# MainBoard_Schematic.net
KiCad netlist of a schematic drawn in Altium Designer
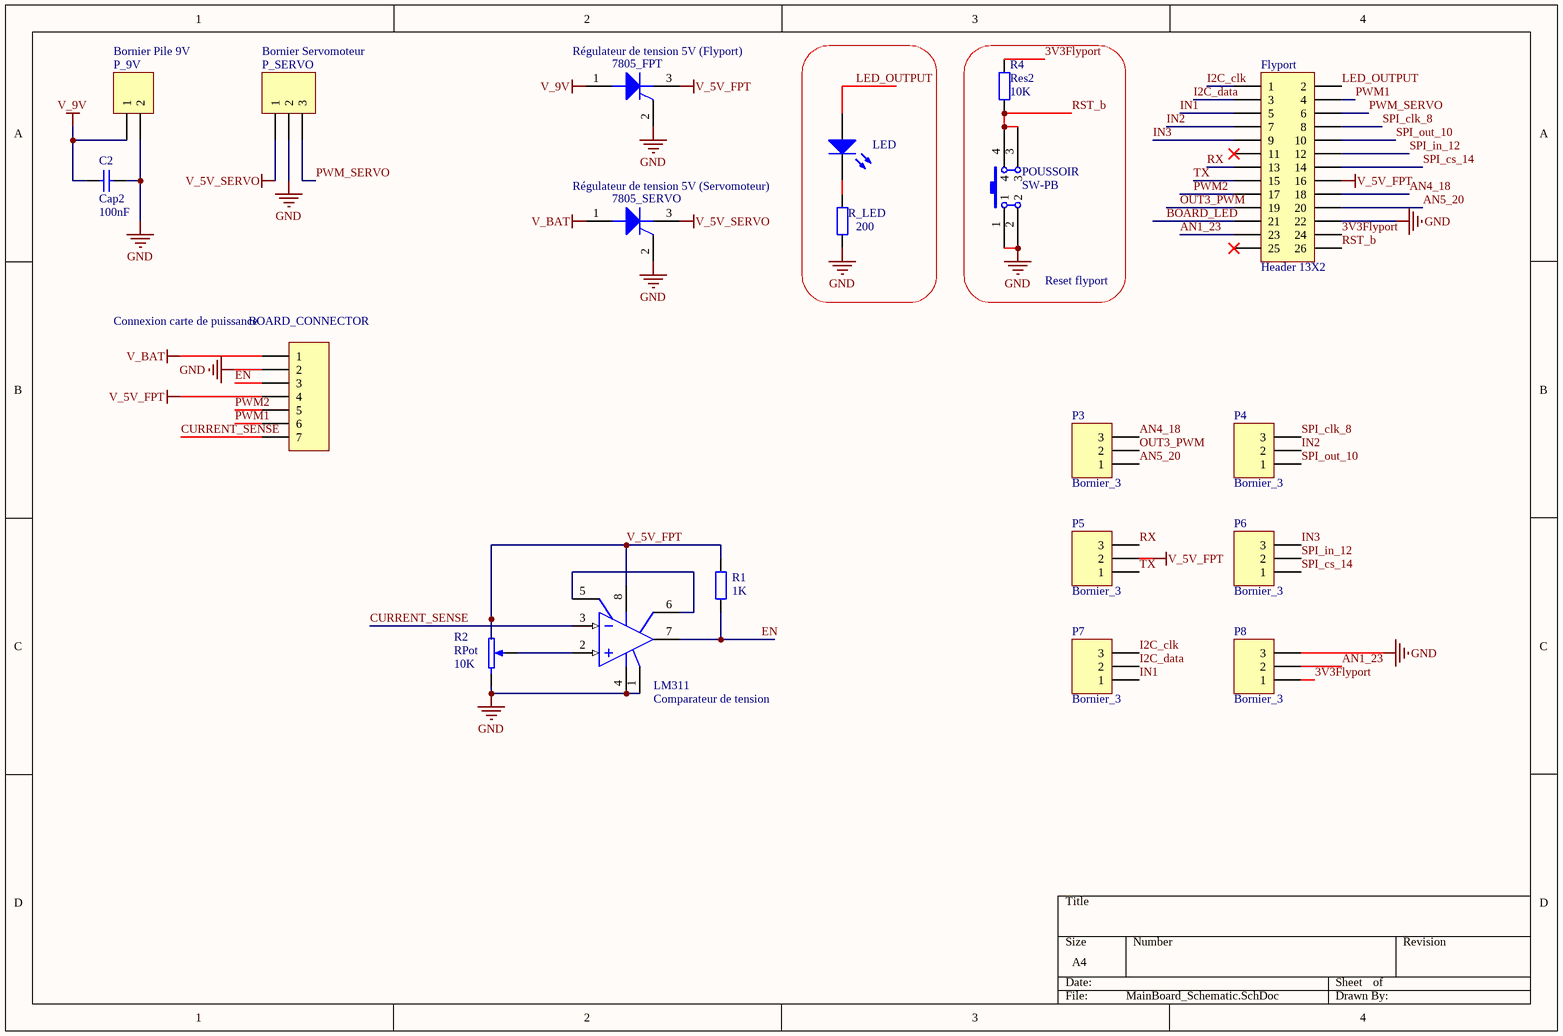
[diagram p0: MainBoard_Schematic.SchDoc]

(export (version "E")
  (design (tool "Eeschema 10.0.6"))
  (components
    (comp (ref "7805_FPT")
      (value "Régulateur de tension 5V (Flyport)")
      (footprint "TO-220-AB")
      (description "Silicon Controlled Rectifier")
      (fields (field (name "PUBLISHER") "Altium Limited"))
      (libsource (lib "Miscellaneous Devices") (part "SCR"))
    )
    (comp (ref "7805_SERVO")
      (value "Régulateur de tension 5V (Servomoteur)")
      (footprint "TO-220-AB")
      (description "Silicon Controlled Rectifier")
      (fields (field (name "PUBLISHER") "Altium Limited"))
      (libsource (lib "Miscellaneous Devices") (part "SCR"))
    )
    (comp (ref "BOARD_CONNECTOR")
      (value "Connexion carte de puissance")
      (footprint "HDR1X7")
      (description "Header, 7-Pin")
      (fields (field (name "PUBLISHER") "Altium Limited"))
      (libsource (lib "Miscellaneous Connectors") (part "Header 7"))
    )
    (comp (ref "C2")
      (value "Cap2")
      (footprint "CAPA2")
      (description "Capacitor")
      (fields (field (name "ALTIUM_VALUE") "100nF") (field (name "PUBLISHER") "Altium Limited"))
      (libsource (lib "LIBRAIRIE_INTEGREE_PHELMA1") (part "Cap2"))
    )
    (comp (ref "Flyport")
      (value "Header 13X2")
      (footprint "HDR2X13")
      (description "Header, 13-Pin, Dual row")
      (fields (field (name "PUBLISHER") "Altium Limited"))
      (libsource (lib "Miscellaneous Connectors") (part "Header 13X2"))
    )
    (comp (ref "LED")
      (value "Led")
      (footprint "LED")
      (description "LED")
      (fields (field (name "PUBLISHER") "Altium Limited"))
      (libsource (lib "LIBRAIRIE_INTEGREE_PHELMA1") (part "Led"))
    )
    (comp (ref "LM311")
      (value "Comparateur de tension")
      (footprint "LIBRAIRIE_INTEGREE_PHELMA1:DIP8")
      (description "Voltage Comparator")
      (fields (field (name "PUBLISHER") "Altium Limited"))
      (libsource (lib "LIBRAIRIE_INTEGREE_PHELMA1") (part "LM311N"))
    )
    (comp (ref "P3")
      (value "Bornier_3")
      (footprint "Bornier_3")
      (description "Header, 3-Pin")
      (fields (field (name "PUBLISHER") "Altium Limited"))
      (libsource (lib "INTEGRATED_LIBRARY1_CONNECTEURS") (part "Bornier_3"))
    )
    (comp (ref "P4")
      (value "Bornier_3")
      (footprint "Bornier_3")
      (description "Header, 3-Pin")
      (fields (field (name "PUBLISHER") "Altium Limited"))
      (libsource (lib "INTEGRATED_LIBRARY1_CONNECTEURS") (part "Bornier_3"))
    )
    (comp (ref "P5")
      (value "Bornier_3")
      (footprint "Bornier_3")
      (description "Header, 3-Pin")
      (fields (field (name "PUBLISHER") "Altium Limited"))
      (libsource (lib "INTEGRATED_LIBRARY1_CONNECTEURS") (part "Bornier_3"))
    )
    (comp (ref "P6")
      (value "Bornier_3")
      (footprint "Bornier_3")
      (description "Header, 3-Pin")
      (fields (field (name "PUBLISHER") "Altium Limited"))
      (libsource (lib "INTEGRATED_LIBRARY1_CONNECTEURS") (part "Bornier_3"))
    )
    (comp (ref "P7")
      (value "Bornier_3")
      (footprint "Bornier_3")
      (description "Header, 3-Pin")
      (fields (field (name "PUBLISHER") "Altium Limited"))
      (libsource (lib "INTEGRATED_LIBRARY1_CONNECTEURS") (part "Bornier_3"))
    )
    (comp (ref "P8")
      (value "Bornier_3")
      (footprint "Bornier_3")
      (description "Header, 3-Pin")
      (fields (field (name "PUBLISHER") "Altium Limited"))
      (libsource (lib "INTEGRATED_LIBRARY1_CONNECTEURS") (part "Bornier_3"))
    )
    (comp (ref "POUSSOIR")
      (value "SW-PB")
      (footprint "SW_BP")
      (description "Switch")
      (fields (field (name "PUBLISHER") "Altium Limited"))
      (libsource (lib "INTEGRATED_LIBRARY1_CONNECTEURS") (part "SW-PB"))
    )
    (comp (ref "P_9V")
      (value "Bornier Pile 9V")
      (footprint "Bornier_2")
      (description "Header, 2-Pin")
      (fields (field (name "PUBLISHER") "Altium Limited"))
      (libsource (lib "INTEGRATED_LIBRARY1_CONNECTEURS") (part "Bornier_2"))
    )
    (comp (ref "P_SERVO")
      (value "Bornier Servomoteur")
      (footprint "Bornier_3")
      (description "Header, 3-Pin")
      (fields (field (name "PUBLISHER") "Altium Limited"))
      (libsource (lib "") (part "Bornier_3_1"))
    )
    (comp (ref "R1")
      (value "1K")
      (footprint "res5_1/4W")
      (description "Resistor")
      (fields (field (name "Comment") "Res2") (field (name "PUBLISHER") "Altium Limited"))
      (libsource (lib "LIBRAIRIE_INTEGREE_PHELMA1") (part "Res2"))
    )
    (comp (ref "R2")
      (value "RPot")
      (footprint "AJUSTABLE")
      (description "Potentiometer")
      (fields (field (name "ALTIUM_VALUE") "10K") (field (name "PUBLISHER") "Altium Limited"))
      (libsource (lib "LIBRAIRIE_INTEGREE_PHELMA1") (part "RPot"))
    )
    (comp (ref "R4")
      (value "Res2")
      (footprint "res5_1/4W")
      (description "Resistor")
      (fields (field (name "ALTIUM_VALUE") "10K") (field (name "PUBLISHER") "Altium Limited"))
      (libsource (lib "") (part "Res2_1"))
    )
    (comp (ref "R_LED")
      (value "200")
      (footprint "res5_1/4W")
      (description "Resistor")
      (fields (field (name "PUBLISHER") "Altium Limited"))
      (libsource (lib "") (part "Res2_1"))
    )
  )
  (nets
    (net (code "1") (name "/3V3Flyport") (class "Default")
      (node (ref "Flyport") (pin "24") (pinfunction "24_24") (pintype "passive"))
      (node (ref "P8") (pin "1") (pinfunction "1_1") (pintype "passive"))
      (node (ref "R4") (pin "1") (pinfunction "1_1") (pintype "passive"))
    )
    (net (code "2") (name "/AN1_23") (class "Default")
      (node (ref "Flyport") (pin "23") (pinfunction "23_23") (pintype "passive"))
      (node (ref "P8") (pin "2") (pinfunction "2_2") (pintype "passive"))
    )
    (net (code "3") (name "/AN4_18") (class "Default")
      (node (ref "Flyport") (pin "18") (pinfunction "18_18") (pintype "passive"))
      (node (ref "P3") (pin "3") (pinfunction "3_3") (pintype "passive"))
    )
    (net (code "4") (name "/AN5_20") (class "Default")
      (node (ref "Flyport") (pin "20") (pinfunction "20_20") (pintype "passive"))
      (node (ref "P3") (pin "1") (pinfunction "1_1") (pintype "passive"))
    )
    (net (code "5") (name "/BOARD_LED") (class "Default")
      (node (ref "Flyport") (pin "21") (pinfunction "21_21") (pintype "passive"))
    )
    (net (code "6") (name "/CURRENT_SENSE") (class "Default")
      (node (ref "BOARD_CONNECTOR") (pin "7") (pinfunction "7_7") (pintype "passive"))
      (node (ref "LM311") (pin "3") (pinfunction "IN-_3") (pintype "input"))
    )
    (net (code "7") (name "/EN") (class "Default")
      (node (ref "BOARD_CONNECTOR") (pin "3") (pinfunction "3_3") (pintype "passive"))
      (node (ref "LM311") (pin "7") (pinfunction "OUT_7") (pintype "open_collector"))
      (node (ref "R1") (pin "1") (pinfunction "1_1") (pintype "passive"))
    )
    (net (code "8") (name "/I2C_clk") (class "Default")
      (node (ref "Flyport") (pin "1") (pinfunction "1_1") (pintype "passive"))
      (node (ref "P7") (pin "3") (pinfunction "3_3") (pintype "passive"))
    )
    (net (code "9") (name "/I2C_data") (class "Default")
      (node (ref "Flyport") (pin "3") (pinfunction "3_3") (pintype "passive"))
      (node (ref "P7") (pin "2") (pinfunction "2_2") (pintype "passive"))
    )
    (net (code "10") (name "/IN1") (class "Default")
      (node (ref "Flyport") (pin "5") (pinfunction "5_5") (pintype "passive"))
      (node (ref "P7") (pin "1") (pinfunction "1_1") (pintype "passive"))
    )
    (net (code "11") (name "/IN2") (class "Default")
      (node (ref "Flyport") (pin "7") (pinfunction "7_7") (pintype "passive"))
      (node (ref "P4") (pin "2") (pinfunction "2_2") (pintype "passive"))
    )
    (net (code "12") (name "/IN3") (class "Default")
      (node (ref "Flyport") (pin "9") (pinfunction "9_9") (pintype "passive"))
      (node (ref "P6") (pin "3") (pinfunction "3_3") (pintype "passive"))
    )
    (net (code "13") (name "/LED_OUTPUT") (class "Default")
      (node (ref "Flyport") (pin "2") (pinfunction "2_2") (pintype "passive"))
      (node (ref "LED") (pin "1") (pinfunction "A_1") (pintype "passive"))
    )
    (net (code "14") (name "/OUT3_PWM") (class "Default")
      (node (ref "Flyport") (pin "19") (pinfunction "19_19") (pintype "passive"))
      (node (ref "P3") (pin "2") (pinfunction "2_2") (pintype "passive"))
    )
    (net (code "15") (name "/PWM1") (class "Default")
      (node (ref "BOARD_CONNECTOR") (pin "6") (pinfunction "6_6") (pintype "passive"))
      (node (ref "Flyport") (pin "4") (pinfunction "4_4") (pintype "passive"))
    )
    (net (code "16") (name "/PWM2") (class "Default")
      (node (ref "BOARD_CONNECTOR") (pin "5") (pinfunction "5_5") (pintype "passive"))
      (node (ref "Flyport") (pin "17") (pinfunction "17_17") (pintype "passive"))
    )
    (net (code "17") (name "/PWM_SERVO") (class "Default")
      (node (ref "Flyport") (pin "6") (pinfunction "6_6") (pintype "passive"))
      (node (ref "P_SERVO") (pin "3") (pinfunction "3_3") (pintype "passive"))
    )
    (net (code "18") (name "/RST_b") (class "Default")
      (node (ref "Flyport") (pin "26") (pinfunction "26_26") (pintype "passive"))
      (node (ref "POUSSOIR") (pin "3") (pinfunction "3_3") (pintype "passive"))
      (node (ref "POUSSOIR") (pin "4") (pinfunction "4_4") (pintype "passive"))
      (node (ref "R4") (pin "2") (pinfunction "2_2") (pintype "passive"))
    )
    (net (code "19") (name "/RX") (class "Default")
      (node (ref "Flyport") (pin "13") (pinfunction "13_13") (pintype "passive"))
      (node (ref "P5") (pin "3") (pinfunction "3_3") (pintype "passive"))
    )
    (net (code "20") (name "/SPI_clk_8") (class "Default")
      (node (ref "Flyport") (pin "8") (pinfunction "8_8") (pintype "passive"))
      (node (ref "P4") (pin "3") (pinfunction "3_3") (pintype "passive"))
    )
    (net (code "21") (name "/SPI_cs_14") (class "Default")
      (node (ref "Flyport") (pin "14") (pinfunction "14_14") (pintype "passive"))
      (node (ref "P6") (pin "1") (pinfunction "1_1") (pintype "passive"))
    )
    (net (code "22") (name "/SPI_in_12") (class "Default")
      (node (ref "Flyport") (pin "12") (pinfunction "12_12") (pintype "passive"))
      (node (ref "P6") (pin "2") (pinfunction "2_2") (pintype "passive"))
    )
    (net (code "23") (name "/SPI_out_10") (class "Default")
      (node (ref "Flyport") (pin "10") (pinfunction "10_10") (pintype "passive"))
      (node (ref "P4") (pin "1") (pinfunction "1_1") (pintype "passive"))
    )
    (net (code "24") (name "/TX") (class "Default")
      (node (ref "Flyport") (pin "15") (pinfunction "15_15") (pintype "passive"))
      (node (ref "P5") (pin "1") (pinfunction "1_1") (pintype "passive"))
    )
    (net (code "25") (name "GND") (class "Default")
      (node (ref "7805_FPT") (pin "2") (pinfunction "GND_2") (pintype "power_in"))
      (node (ref "7805_SERVO") (pin "2") (pinfunction "GND_2") (pintype "power_in"))
      (node (ref "BOARD_CONNECTOR") (pin "2") (pinfunction "2_2") (pintype "passive"))
      (node (ref "C2") (pin "2") (pinfunction "2_2") (pintype "passive"))
      (node (ref "Flyport") (pin "22") (pinfunction "22_22") (pintype "passive"))
      (node (ref "LM311") (pin "1") (pinfunction "GND_1") (pintype "power_in"))
      (node (ref "LM311") (pin "4") (pinfunction "V-_(CASE)_4") (pintype "power_in"))
      (node (ref "P8") (pin "3") (pinfunction "3_3") (pintype "passive"))
      (node (ref "POUSSOIR") (pin "1") (pinfunction "1_1") (pintype "passive"))
      (node (ref "POUSSOIR") (pin "2") (pinfunction "2_2") (pintype "passive"))
      (node (ref "P_9V") (pin "2") (pinfunction "2_2") (pintype "passive"))
      (node (ref "P_SERVO") (pin "2") (pinfunction "2_2") (pintype "passive"))
      (node (ref "R2") (pin "3") (pinfunction "TOP_3") (pintype "passive"))
      (node (ref "R_LED") (pin "2") (pinfunction "2_2") (pintype "passive"))
    )
    (net (code "26") (name "Net-(LED-K)") (class "Default")
      (node (ref "LED") (pin "2") (pinfunction "K_2") (pintype "passive"))
      (node (ref "R_LED") (pin "1") (pinfunction "1_1") (pintype "passive"))
    )
    (net (code "27") (name "Net-(LM311-BAL)") (class "Default")
      (node (ref "LM311") (pin "5") (pinfunction "BAL_5") (pintype "passive"))
      (node (ref "LM311") (pin "6") (pinfunction "BAL/STB_6") (pintype "passive"))
    )
    (net (code "28") (name "Net-(LM311-IN+)") (class "Default")
      (node (ref "LM311") (pin "2") (pinfunction "IN+_2") (pintype "input"))
      (node (ref "R2") (pin "2") (pinfunction "TAP_2") (pintype "passive"))
    )
    (net (code "29") (name "V_5V_FPT") (class "Default")
      (node (ref "7805_FPT") (pin "3") (pinfunction "OUT_3") (pintype "power_in"))
      (node (ref "BOARD_CONNECTOR") (pin "4") (pinfunction "4_4") (pintype "passive"))
      (node (ref "Flyport") (pin "16") (pinfunction "16_16") (pintype "passive"))
      (node (ref "LM311") (pin "8") (pinfunction "V+_8") (pintype "power_in"))
      (node (ref "P5") (pin "2") (pinfunction "2_2") (pintype "passive"))
      (node (ref "R1") (pin "2") (pinfunction "2_2") (pintype "passive"))
      (node (ref "R2") (pin "1") (pinfunction "BOT_1") (pintype "passive"))
    )
    (net (code "30") (name "V_5V_SERVO") (class "Default")
      (node (ref "7805_SERVO") (pin "3") (pinfunction "OUT_3") (pintype "power_in"))
      (node (ref "P_SERVO") (pin "1") (pinfunction "1_1") (pintype "passive"))
    )
    (net (code "31") (name "V_9V") (class "Default")
      (node (ref "7805_FPT") (pin "1") (pinfunction "IN_1") (pintype "power_in"))
      (node (ref "C2") (pin "1") (pinfunction "1_1") (pintype "passive"))
      (node (ref "P_9V") (pin "1") (pinfunction "1_1") (pintype "passive"))
    )
    (net (code "32") (name "V_BAT") (class "Default")
      (node (ref "7805_SERVO") (pin "1") (pinfunction "IN_1") (pintype "power_in"))
      (node (ref "BOARD_CONNECTOR") (pin "1") (pinfunction "1_1") (pintype "passive"))
    )
    (net (code "33") (name "unconnected-(Flyport-Pad11)") (class "Default")
      (node (ref "Flyport") (pin "11") (pinfunction "11_11") (pintype "passive+no_connect"))
    )
    (net (code "34") (name "unconnected-(Flyport-Pad25)") (class "Default")
      (node (ref "Flyport") (pin "25") (pinfunction "25_25") (pintype "passive+no_connect"))
    )
  )
)
